# ICS40300-preamp-surfacemount_Rev-A.net
KiCad netlist of a schematic drawn in EAGLE
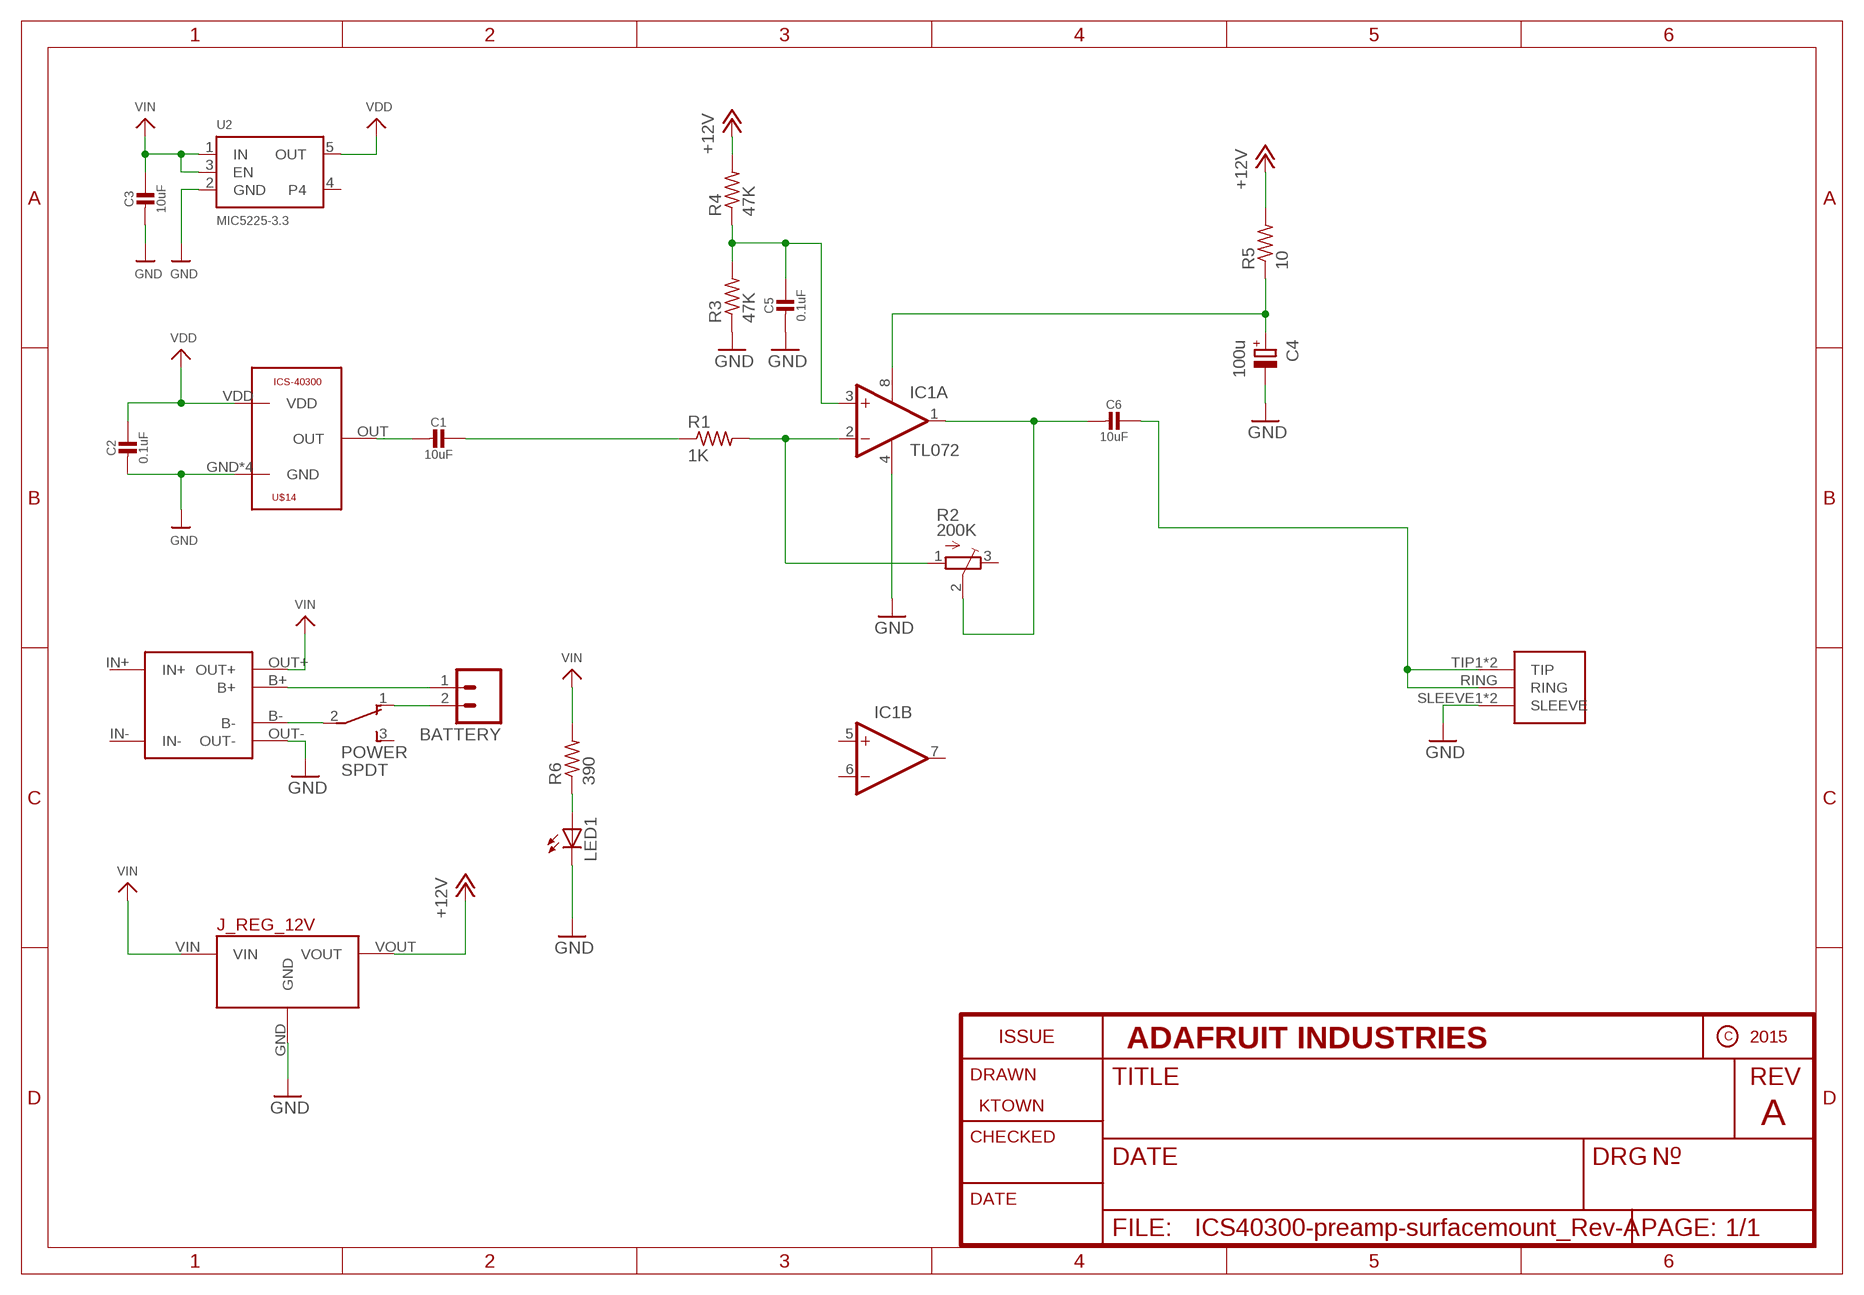
[diagram p0: schematic, sheet 1]

(export (version "E")
  (design (tool "Eeschema 10.0.6"))
  (components
    (comp (ref "BATTERY")
      (value "M02LOCK")
      (footprint "eagle-import:1X02_LOCK")
      (libsource (lib "eagle-import") (part "M02LOCK"))
    )
    (comp (ref "C1")
      (value "10uF")
      (footprint "eagle-import:0805-NO")
      (libsource (lib "eagle-import") (part "CAP_CERAMIC0805-NOOUTLINE"))
    )
    (comp (ref "C2")
      (value "0.1uF")
      (footprint "eagle-import:0805-NO")
      (libsource (lib "eagle-import") (part "CAP_CERAMIC0805-NOOUTLINE"))
    )
    (comp (ref "C3")
      (value "10uF")
      (footprint "eagle-import:0805-NO")
      (libsource (lib "eagle-import") (part "CAP_CERAMIC0805-NOOUTLINE"))
    )
    (comp (ref "C4")
      (value "100u")
      (footprint "eagle-import:TT2D4L")
      (libsource (lib "eagle-import") (part "CPOL-EUTT2D4L"))
    )
    (comp (ref "C5")
      (value "0.1uF")
      (footprint "eagle-import:0805-NO")
      (libsource (lib "eagle-import") (part "CAP_CERAMIC0805-NOOUTLINE"))
    )
    (comp (ref "C6")
      (value "10uF")
      (footprint "eagle-import:0805-NO")
      (libsource (lib "eagle-import") (part "CAP_CERAMIC0805-NOOUTLINE"))
    )
    (comp (ref "IC1")
      (value "TL072")
      (footprint "eagle-import:SO08")
      (fields (field (name "IC_NAME") "TL072"))
      (libsource (lib "eagle-import") (part "OPA2UA134"))
    )
    (comp (ref "J_REG_12V")
      (value "POLOLU_VOLTAGE_REGULATORS_3PIN")
      (footprint "eagle-import:POLOLU_5V-12V_STEPUP_U3V12F5-U3V12F12")
      (libsource (lib "eagle-import") (part "POLOLU_VOLTAGE_REGULATORS_3PIN"))
    )
    (comp (ref "LED1")
      (value "LED3MM")
      (footprint "eagle-import:LED3MM")
      (libsource (lib "eagle-import") (part "LED3MM"))
    )
    (comp (ref "POWER")
      (value "SPDT")
      (footprint "eagle-import:SWITCH_SPDT-TE-CONNECT")
      (libsource (lib "eagle-import") (part "SWITCH_SPDTTE-CONNECT"))
    )
    (comp (ref "R1")
      (value "1K")
      (footprint "eagle-import:R0805")
      (libsource (lib "eagle-import") (part "R-US_R0805"))
    )
    (comp (ref "R2")
      (value "200K")
      (footprint "eagle-import:TRIM-3386")
      (libsource (lib "eagle-import") (part "TRIMPOT3386"))
    )
    (comp (ref "R3")
      (value "47K")
      (footprint "eagle-import:R0805")
      (libsource (lib "eagle-import") (part "R-US_R0805"))
    )
    (comp (ref "R4")
      (value "47K")
      (footprint "eagle-import:R0805")
      (libsource (lib "eagle-import") (part "R-US_R0805"))
    )
    (comp (ref "R5")
      (value "10")
      (footprint "eagle-import:R0805")
      (libsource (lib "eagle-import") (part "R-US_R0805"))
    )
    (comp (ref "R6")
      (value "390")
      (footprint "eagle-import:R0805")
      (libsource (lib "eagle-import") (part "R-US_R0805"))
    )
    (comp (ref "U$13")
      (value "1/8\"-F-STEREO-PCB")
      (footprint "eagle-import:1_8_-F-STEREO-PCB")
      (libsource (lib "eagle-import") (part "1/8{dblquote}-F-STEREO-PCB"))
    )
    (comp (ref "U$14")
      (value "ICS-40300")
      (footprint "eagle-import:ICS-40300")
      (libsource (lib "eagle-import") (part "ICS-40300"))
    )
    (comp (ref "U2")
      (value "MIC5225-3.3")
      (footprint "eagle-import:SOT23-5")
      (libsource (lib "eagle-import") (part "VREG_SOT23-5"))
    )
    (comp (ref "USB-LIPO-CHARGER")
      (value "TP4056-MODULE")
      (footprint "eagle-import:TP4056-LITHIUM-PROTECTED-MODULE")
      (libsource (lib "eagle-import") (part "TP4056-MODULE"))
    )
  )
  (nets
    (net (code "1") (name "+12V") (class "Default")
      (node (ref "J_REG_12V") (pin "VOUT") (pinfunction "VOUT_VOUT") (pintype "bidirectional"))
      (node (ref "R4") (pin "2") (pinfunction "2_2") (pintype "passive"))
      (node (ref "R5") (pin "2") (pinfunction "2_2") (pintype "passive"))
    )
    (net (code "2") (name "/IN+") (class "Default")
      (node (ref "USB-LIPO-CHARGER") (pin "IN+") (pinfunction "IN+_IN+") (pintype "power_in"))
    )
    (net (code "3") (name "/IN-") (class "Default")
      (node (ref "USB-LIPO-CHARGER") (pin "IN-") (pinfunction "IN-_IN-") (pintype "power_in"))
    )
    (net (code "4") (name "GND") (class "Default")
      (node (ref "C2") (pin "2") (pinfunction "2_2") (pintype "passive"))
      (node (ref "C3") (pin "2") (pinfunction "2_2") (pintype "passive"))
      (node (ref "C4") (pin "-") (pinfunction "-_-") (pintype "passive"))
      (node (ref "C5") (pin "2") (pinfunction "2_2") (pintype "passive"))
      (node (ref "IC1") (pin "4") (pinfunction "V-_4") (pintype "power_in"))
      (node (ref "J_REG_12V") (pin "GND") (pinfunction "GND_GND") (pintype "bidirectional"))
      (node (ref "LED1") (pin "K") (pinfunction "C_K") (pintype "passive"))
      (node (ref "R3") (pin "1") (pinfunction "1_1") (pintype "passive"))
      (node (ref "U$13") (pin "SLEEVE1") (pinfunction "SLEEVE_SLEEVE1") (pintype "bidirectional"))
      (node (ref "U$13") (pin "SLEEVE2") (pinfunction "SLEEVE_SLEEVE2") (pintype "bidirectional"))
      (node (ref "U$14") (pin "GND") (pinfunction "GND_GND") (pintype "bidirectional"))
      (node (ref "U$14") (pin "GND1") (pinfunction "GND_GND1") (pintype "bidirectional"))
      (node (ref "U$14") (pin "GND2") (pinfunction "GND_GND2") (pintype "bidirectional"))
      (node (ref "U$14") (pin "GND3") (pinfunction "GND_GND3") (pintype "bidirectional"))
      (node (ref "U2") (pin "2") (pinfunction "GND_2") (pintype "power_in"))
      (node (ref "USB-LIPO-CHARGER") (pin "OUT-") (pinfunction "OUT-_OUT-") (pintype "power_in"))
    )
    (net (code "5") (name "Net-(BATTERY-Pad1)") (class "Default")
      (node (ref "BATTERY") (pin "1") (pinfunction "1_1") (pintype "passive"))
      (node (ref "USB-LIPO-CHARGER") (pin "B+") (pinfunction "B+_B+") (pintype "power_in"))
    )
    (net (code "6") (name "Net-(BATTERY-Pad2)") (class "Default")
      (node (ref "BATTERY") (pin "2") (pinfunction "2_2") (pintype "passive"))
      (node (ref "POWER") (pin "1") (pinfunction "1_1") (pintype "passive"))
    )
    (net (code "7") (name "Net-(C1-Pad1)") (class "Default")
      (node (ref "C1") (pin "1") (pinfunction "1_1") (pintype "passive"))
      (node (ref "R1") (pin "1") (pinfunction "1_1") (pintype "passive"))
    )
    (net (code "8") (name "Net-(C1-Pad2)") (class "Default")
      (node (ref "C1") (pin "2") (pinfunction "2_2") (pintype "passive"))
      (node (ref "U$14") (pin "OUT") (pinfunction "OUT_OUT") (pintype "bidirectional"))
    )
    (net (code "9") (name "Net-(C6-Pad1)") (class "Default")
      (node (ref "C6") (pin "1") (pinfunction "1_1") (pintype "passive"))
      (node (ref "U$13") (pin "RING") (pinfunction "RING_RING") (pintype "bidirectional"))
      (node (ref "U$13") (pin "TIP1") (pinfunction "TIP_TIP1") (pintype "bidirectional"))
      (node (ref "U$13") (pin "TIP2") (pinfunction "TIP_TIP2") (pintype "bidirectional"))
    )
    (net (code "10") (name "Net-(IC1A-+IN)") (class "Default")
      (node (ref "C5") (pin "1") (pinfunction "1_1") (pintype "passive"))
      (node (ref "IC1") (pin "3") (pinfunction "+IN_3") (pintype "input"))
      (node (ref "R3") (pin "2") (pinfunction "2_2") (pintype "passive"))
      (node (ref "R4") (pin "1") (pinfunction "1_1") (pintype "passive"))
    )
    (net (code "11") (name "Net-(IC1A--IN)") (class "Default")
      (node (ref "IC1") (pin "2") (pinfunction "-IN_2") (pintype "input"))
      (node (ref "R1") (pin "2") (pinfunction "2_2") (pintype "passive"))
      (node (ref "R2") (pin "1") (pinfunction "A_1") (pintype "passive"))
    )
    (net (code "12") (name "Net-(IC1A-OUT)") (class "Default")
      (node (ref "C6") (pin "2") (pinfunction "2_2") (pintype "passive"))
      (node (ref "IC1") (pin "1") (pinfunction "OUT_1") (pintype "output"))
      (node (ref "R2") (pin "2") (pinfunction "S_2") (pintype "passive"))
    )
    (net (code "13") (name "Net-(IC1A-V+)") (class "Default")
      (node (ref "C4") (pin "+") (pinfunction "+_+") (pintype "passive"))
      (node (ref "IC1") (pin "8") (pinfunction "V+_8") (pintype "power_in"))
      (node (ref "R5") (pin "1") (pinfunction "1_1") (pintype "passive"))
    )
    (net (code "14") (name "Net-(LED1-PadA)") (class "Default")
      (node (ref "LED1") (pin "A") (pinfunction "A_A") (pintype "passive"))
      (node (ref "R6") (pin "1") (pinfunction "1_1") (pintype "passive"))
    )
    (net (code "15") (name "Net-(POWER-Pad2)") (class "Default")
      (node (ref "POWER") (pin "2") (pinfunction "2_2") (pintype "passive"))
      (node (ref "USB-LIPO-CHARGER") (pin "B-") (pinfunction "B-_B-") (pintype "power_in"))
    )
    (net (code "16") (name "VDD") (class "Default")
      (node (ref "C2") (pin "1") (pinfunction "1_1") (pintype "passive"))
      (node (ref "U$14") (pin "VDD") (pinfunction "VDD_VDD") (pintype "bidirectional"))
      (node (ref "U2") (pin "5") (pinfunction "OUT_5") (pintype "power_in"))
    )
    (net (code "17") (name "VIN") (class "Default")
      (node (ref "C3") (pin "1") (pinfunction "1_1") (pintype "passive"))
      (node (ref "J_REG_12V") (pin "VIN") (pinfunction "VIN_VIN") (pintype "bidirectional"))
      (node (ref "R6") (pin "2") (pinfunction "2_2") (pintype "passive"))
      (node (ref "U2") (pin "1") (pinfunction "IN_1") (pintype "power_in"))
      (node (ref "U2") (pin "3") (pinfunction "EN_3") (pintype "input"))
      (node (ref "USB-LIPO-CHARGER") (pin "OUT+") (pinfunction "OUT+_OUT+") (pintype "power_in"))
    )
    (net (code "18") (name "unconnected-(IC1B-+IN-Pad5)") (class "Default")
      (node (ref "IC1") (pin "5") (pinfunction "+IN_5") (pintype "input"))
    )
    (net (code "19") (name "unconnected-(IC1B--IN-Pad6)") (class "Default")
      (node (ref "IC1") (pin "6") (pinfunction "-IN_6") (pintype "input"))
    )
    (net (code "20") (name "unconnected-(IC1B-OUT-Pad7)") (class "Default")
      (node (ref "IC1") (pin "7") (pinfunction "OUT_7") (pintype "output"))
    )
    (net (code "21") (name "unconnected-(POWER-Pad3)") (class "Default")
      (node (ref "POWER") (pin "3") (pinfunction "3_3") (pintype "passive"))
    )
    (net (code "22") (name "unconnected-(R2-E-Pad3)") (class "Default")
      (node (ref "R2") (pin "3") (pinfunction "E_3") (pintype "passive"))
    )
    (net (code "23") (name "unconnected-(U2-P4-Pad4)") (class "Default")
      (node (ref "U2") (pin "4") (pinfunction "P4_4") (pintype "bidirectional"))
    )
  )
)
